# rapidshark-h-bridge-mk-2_0.net
KiCad netlist of a schematic drawn in EAGLE
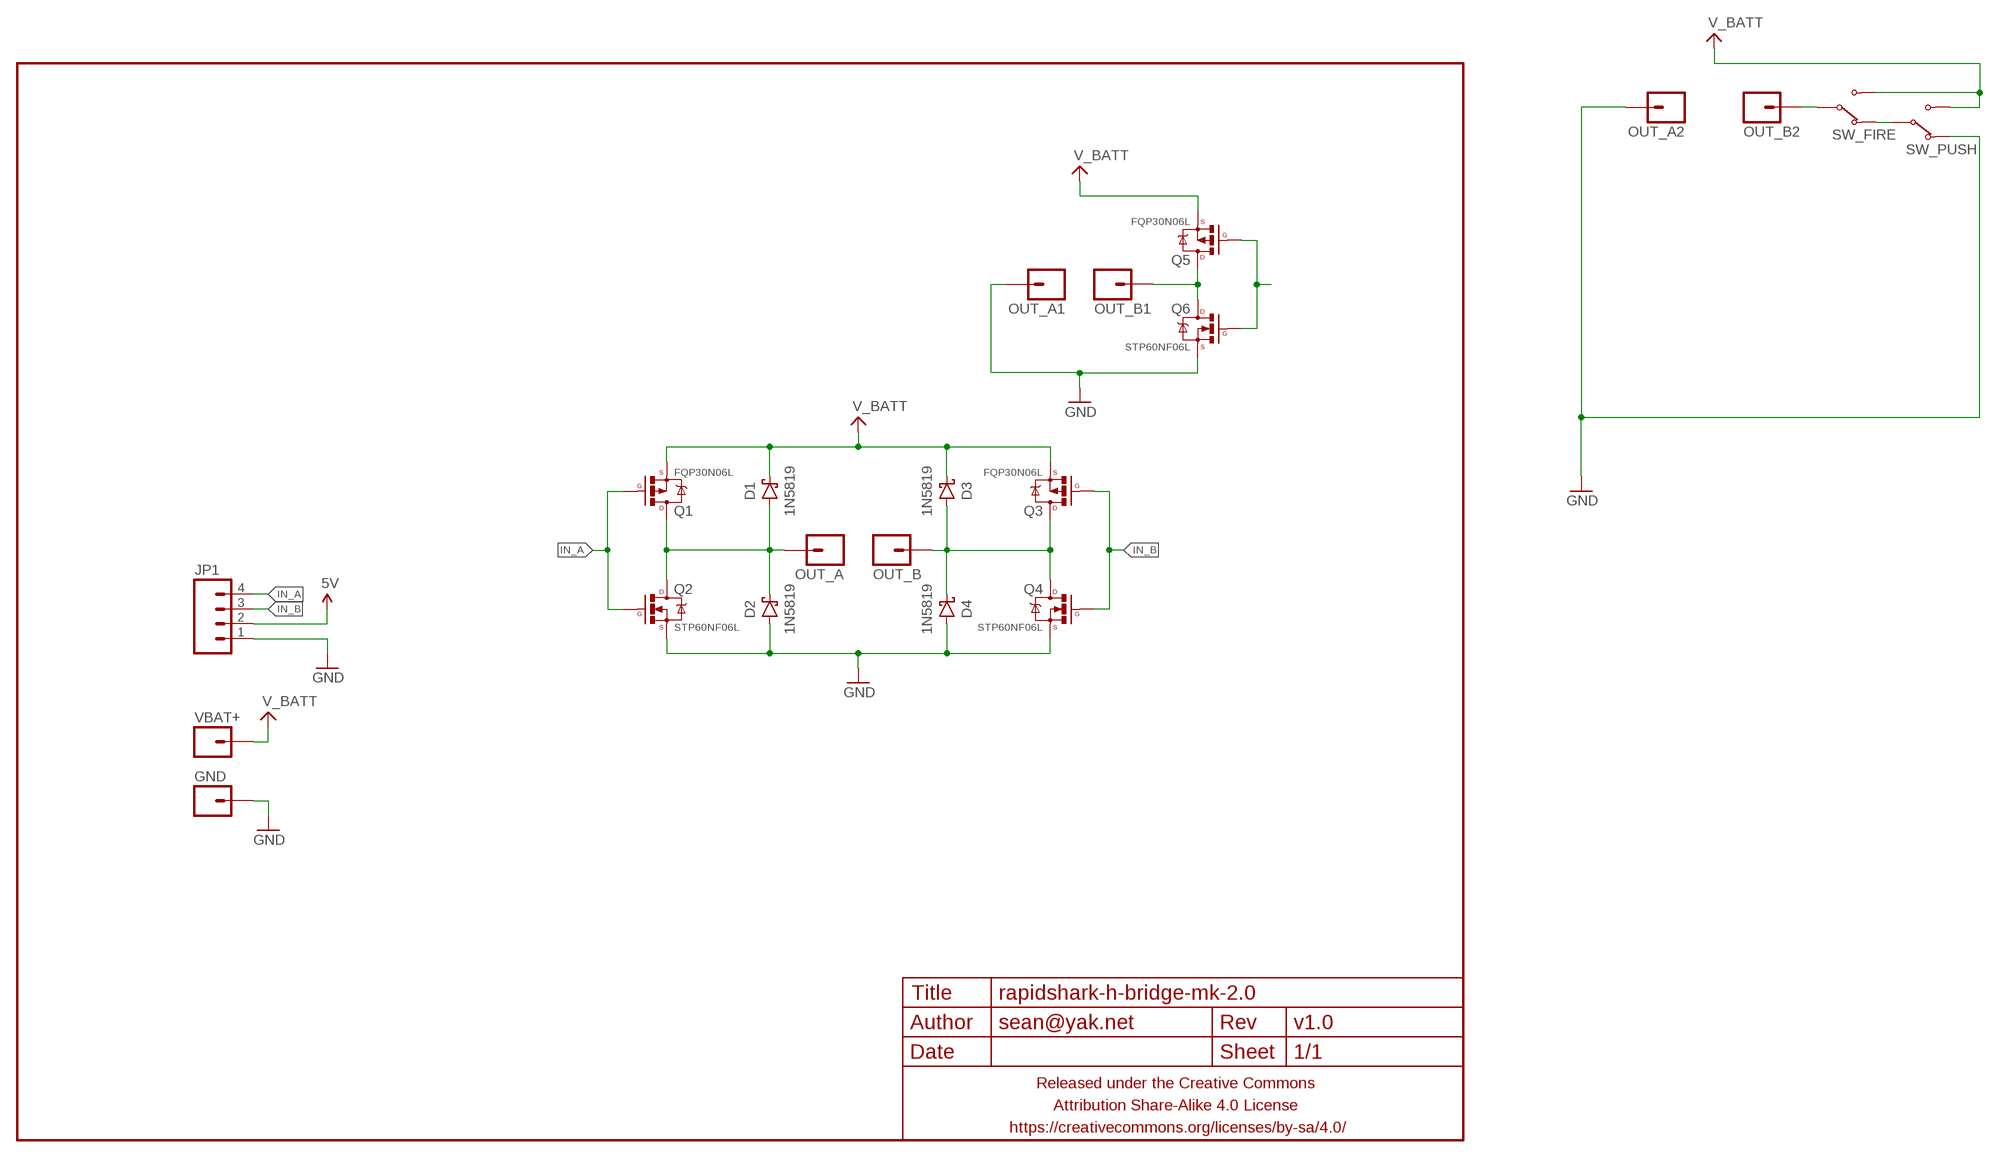
[diagram p0: schematic, sheet 1]

(export (version "E")
  (design (tool "Eeschema 10.0.6"))
  (components
    (comp (ref "D1")
      (value "1N5819")
      (footprint "eagle-import:DIODE-SCHOTTKY-10.16MM")
      (libsource (lib "eagle-import") (part "DIODE-SCHOTTKYPTH-10.16MM"))
    )
    (comp (ref "D2")
      (value "1N5819")
      (footprint "eagle-import:DIODE-SCHOTTKY-10.16MM")
      (libsource (lib "eagle-import") (part "DIODE-SCHOTTKYPTH-10.16MM"))
    )
    (comp (ref "D3")
      (value "1N5819")
      (footprint "eagle-import:DIODE-SCHOTTKY-10.16MM")
      (libsource (lib "eagle-import") (part "DIODE-SCHOTTKYPTH-10.16MM"))
    )
    (comp (ref "D4")
      (value "1N5819")
      (footprint "eagle-import:DIODE-SCHOTTKY-10.16MM")
      (libsource (lib "eagle-import") (part "DIODE-SCHOTTKYPTH-10.16MM"))
    )
    (comp (ref "FRAME1")
      (value "FRAME-LETTERNO_PACKAGE")
      (footprint "eagle-import:DUMMY")
      (fields (field (name "DESIGNER") "sean@yak.net") (field (name "VERSION") "v1.0"))
      (libsource (lib "eagle-import") (part "FRAME-LETTERNO_PACKAGE"))
    )
    (comp (ref "GND")
      (value "M0112AWG")
      (footprint "eagle-import:1X01-12AWG")
      (libsource (lib "eagle-import") (part "M0112AWG"))
    )
    (comp (ref "JP1")
      (value "M04PTH")
      (footprint "eagle-import:1X04-PTH-VERT")
      (libsource (lib "eagle-import") (part "M04PTH"))
    )
    (comp (ref "OUT_A")
      (value "M0112AWG")
      (footprint "eagle-import:1X01-12AWG")
      (libsource (lib "eagle-import") (part "M0112AWG"))
    )
    (comp (ref "OUT_A1")
      (value "M0112AWG")
      (footprint "eagle-import:1X01-12AWG")
      (libsource (lib "eagle-import") (part "M0112AWG"))
    )
    (comp (ref "OUT_A2")
      (value "M0112AWG")
      (footprint "eagle-import:1X01-12AWG")
      (libsource (lib "eagle-import") (part "M0112AWG"))
    )
    (comp (ref "OUT_B")
      (value "M0112AWG")
      (footprint "eagle-import:1X01-12AWG")
      (libsource (lib "eagle-import") (part "M0112AWG"))
    )
    (comp (ref "OUT_B1")
      (value "M0112AWG")
      (footprint "eagle-import:1X01-12AWG")
      (libsource (lib "eagle-import") (part "M0112AWG"))
    )
    (comp (ref "OUT_B2")
      (value "M0112AWG")
      (footprint "eagle-import:1X01-12AWG")
      (libsource (lib "eagle-import") (part "M0112AWG"))
    )
    (comp (ref "Q1")
      (value "FQP30N06L")
      (footprint "eagle-import:TO220-THERMPAD")
      (libsource (lib "eagle-import") (part "MOSFET-PCHANNELTO-220-THERMPAD"))
    )
    (comp (ref "Q2")
      (value "STP60NF06L")
      (footprint "eagle-import:TO220-THERMPAD")
      (libsource (lib "eagle-import") (part "MOSFET-NCHANNELTO-220"))
    )
    (comp (ref "Q3")
      (value "FQP30N06L")
      (footprint "eagle-import:TO220-THERMPAD")
      (libsource (lib "eagle-import") (part "MOSFET-PCHANNELTO-220-THERMPAD"))
    )
    (comp (ref "Q4")
      (value "STP60NF06L")
      (footprint "eagle-import:TO220-THERMPAD")
      (libsource (lib "eagle-import") (part "MOSFET-NCHANNELTO-220"))
    )
    (comp (ref "Q5")
      (value "FQP30N06L")
      (footprint "eagle-import:TO220-THERMPAD")
      (libsource (lib "eagle-import") (part "MOSFET-PCHANNELTO-220-THERMPAD"))
    )
    (comp (ref "Q6")
      (value "STP60NF06L")
      (footprint "eagle-import:TO220-THERMPAD")
      (libsource (lib "eagle-import") (part "MOSFET-NCHANNELTO-220"))
    )
    (comp (ref "SW_FIRE")
      (value "SWITCH-SPDTPTH-VERT-2.54MM")
      (footprint "eagle-import:SWITCH-SPDT")
      (libsource (lib "eagle-import") (part "SWITCH-SPDTPTH-VERT-2.54MM"))
    )
    (comp (ref "SW_PUSH")
      (value "SWITCH-SPDTPTH-VERT-2.54MM")
      (footprint "eagle-import:SWITCH-SPDT")
      (libsource (lib "eagle-import") (part "SWITCH-SPDTPTH-VERT-2.54MM"))
    )
    (comp (ref "VBAT+")
      (value "M0112AWG")
      (footprint "eagle-import:1X01-12AWG")
      (libsource (lib "eagle-import") (part "M0112AWG"))
    )
  )
  (nets
    (net (code "1") (name "5V") (class "Default")
      (node (ref "JP1") (pin "2") (pinfunction "2_2") (pintype "passive"))
    )
    (net (code "2") (name "GND") (class "Default")
      (node (ref "D2") (pin "A") (pinfunction "A_A") (pintype "passive"))
      (node (ref "D4") (pin "A") (pinfunction "A_A") (pintype "passive"))
      (node (ref "GND") (pin "1") (pinfunction "1_1") (pintype "passive"))
      (node (ref "JP1") (pin "1") (pinfunction "1_1") (pintype "passive"))
      (node (ref "OUT_A1") (pin "1") (pinfunction "1_1") (pintype "passive"))
      (node (ref "OUT_A2") (pin "1") (pinfunction "1_1") (pintype "passive"))
      (node (ref "Q2") (pin "3") (pinfunction "S_3") (pintype "passive"))
      (node (ref "Q4") (pin "3") (pinfunction "S_3") (pintype "passive"))
      (node (ref "Q6") (pin "3") (pinfunction "S_3") (pintype "passive"))
      (node (ref "SW_PUSH") (pin "1") (pinfunction "NC_1") (pintype "passive"))
    )
    (net (code "3") (name "IN_A") (class "Default")
      (node (ref "JP1") (pin "4") (pinfunction "4_4") (pintype "passive"))
      (node (ref "Q1") (pin "1") (pinfunction "G_1") (pintype "passive"))
      (node (ref "Q2") (pin "1") (pinfunction "G_1") (pintype "passive"))
    )
    (net (code "4") (name "IN_B") (class "Default")
      (node (ref "JP1") (pin "3") (pinfunction "3_3") (pintype "passive"))
      (node (ref "Q3") (pin "1") (pinfunction "G_1") (pintype "passive"))
      (node (ref "Q4") (pin "1") (pinfunction "G_1") (pintype "passive"))
    )
    (net (code "5") (name "Net-(D1-PadA)") (class "Default")
      (node (ref "D1") (pin "A") (pinfunction "A_A") (pintype "passive"))
      (node (ref "D2") (pin "C") (pinfunction "C_C") (pintype "passive"))
      (node (ref "OUT_A") (pin "1") (pinfunction "1_1") (pintype "passive"))
      (node (ref "Q1") (pin "2@1") (pinfunction "D_2@1") (pintype "passive"))
      (node (ref "Q1") (pin "2@2") (pinfunction "D_2@2") (pintype "passive"))
      (node (ref "Q2") (pin "2@1") (pinfunction "D_2@1") (pintype "passive"))
      (node (ref "Q2") (pin "2@2") (pinfunction "D_2@2") (pintype "passive"))
    )
    (net (code "6") (name "Net-(D3-PadA)") (class "Default")
      (node (ref "D3") (pin "A") (pinfunction "A_A") (pintype "passive"))
      (node (ref "D4") (pin "C") (pinfunction "C_C") (pintype "passive"))
      (node (ref "OUT_B") (pin "1") (pinfunction "1_1") (pintype "passive"))
      (node (ref "Q3") (pin "2@1") (pinfunction "D_2@1") (pintype "passive"))
      (node (ref "Q3") (pin "2@2") (pinfunction "D_2@2") (pintype "passive"))
      (node (ref "Q4") (pin "2@1") (pinfunction "D_2@1") (pintype "passive"))
      (node (ref "Q4") (pin "2@2") (pinfunction "D_2@2") (pintype "passive"))
    )
    (net (code "7") (name "Net-(OUT_B1-Pad1)") (class "Default")
      (node (ref "OUT_B1") (pin "1") (pinfunction "1_1") (pintype "passive"))
      (node (ref "Q5") (pin "2@1") (pinfunction "D_2@1") (pintype "passive"))
      (node (ref "Q5") (pin "2@2") (pinfunction "D_2@2") (pintype "passive"))
      (node (ref "Q6") (pin "2@1") (pinfunction "D_2@1") (pintype "passive"))
      (node (ref "Q6") (pin "2@2") (pinfunction "D_2@2") (pintype "passive"))
    )
    (net (code "8") (name "Net-(Q5-G)") (class "Default")
      (node (ref "Q5") (pin "1") (pinfunction "G_1") (pintype "passive"))
      (node (ref "Q6") (pin "1") (pinfunction "G_1") (pintype "passive"))
    )
    (net (code "9") (name "Net-(SW_FIRE-COM)") (class "Default")
      (node (ref "OUT_B2") (pin "1") (pinfunction "1_1") (pintype "passive"))
      (node (ref "SW_FIRE") (pin "2") (pinfunction "COM_2") (pintype "passive"))
    )
    (net (code "10") (name "Net-(SW_FIRE-NC)") (class "Default")
      (node (ref "SW_FIRE") (pin "1") (pinfunction "NC_1") (pintype "passive"))
      (node (ref "SW_PUSH") (pin "2") (pinfunction "COM_2") (pintype "passive"))
    )
    (net (code "11") (name "V_BATT") (class "Default")
      (node (ref "D1") (pin "C") (pinfunction "C_C") (pintype "passive"))
      (node (ref "D3") (pin "C") (pinfunction "C_C") (pintype "passive"))
      (node (ref "Q1") (pin "3") (pinfunction "S_3") (pintype "passive"))
      (node (ref "Q3") (pin "3") (pinfunction "S_3") (pintype "passive"))
      (node (ref "Q5") (pin "3") (pinfunction "S_3") (pintype "passive"))
      (node (ref "SW_FIRE") (pin "3") (pinfunction "NO_3") (pintype "passive"))
      (node (ref "SW_PUSH") (pin "3") (pinfunction "NO_3") (pintype "passive"))
      (node (ref "VBAT+") (pin "1") (pinfunction "1_1") (pintype "passive"))
    )
  )
)
